# ADJ_REG.net
KiCad netlist of a schematic drawn in Altium Designer
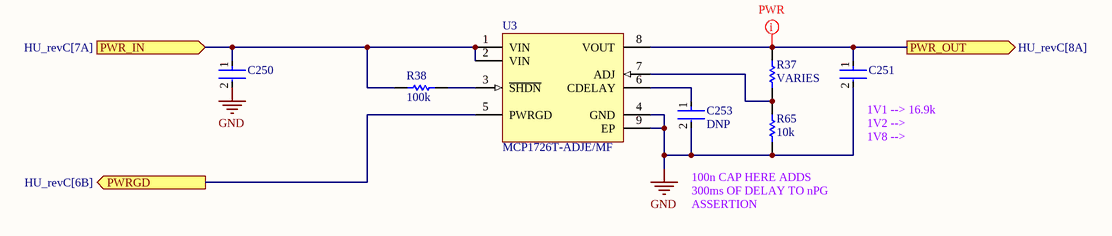
[diagram p0: ADJ_REG.SchDoc]

(export (version "E")
  (design (tool "Eeschema 10.0.6"))
  (components
    (comp (ref "C250")
      (value "C0805C475J4RACAUTO")
      (footprint "FP-C0805C475J4RACAUTO-MFG")
      (description "C0805C475J4RACAUTO Cap Ceramic 4.7uF 16V X7R 5% Pad SMD 0805 125C Automotive T/R")
      (fields (field (name "TOLERANCE") "5%"))
      (libsource (lib "Altium Content Vault") (part "b4654b650e69147ec39a6b967a45e02"))
    )
    (comp (ref "C251")
      (value "GRM21BR61E226ME44L")
      (footprint "FP-GRM21B-0_2-e0_2_0_7-IPC_B")
      (description "Chip Multilayer Ceramic Capacitors for General Purpose, 0805, 22uF, X5R, 15%, 20%, 25V")
      (fields (field (name "TOLERANCE") "20%") (field (name "VOLTAGE") "25V"))
      (libsource (lib "Altium Content Vault") (part "b4654b650e69147ec39a6b967a45e02"))
    )
    (comp (ref "C253")
      (value "DNP")
      (footprint "FP-0402-L_1_0_0_05-W_0_5-IPC_A")
      (description "LARGE PADS, 0402 CAP, CHANGE COMMENT TO MATCH REAL P/N")
      (libsource (lib "Space Concordia") (part "b4654b650e69147ec39a6b967a45e02"))
    )
    (comp (ref "R37")
      (value "VARIES")
      (footprint "R0603B")
      (description "Resistor")
      (libsource (lib "Space Concordia") (part "Resistor"))
    )
    (comp (ref "R38")
      (value "100k")
      (footprint "R0603B")
      (description "Resistor")
      (libsource (lib "Space Concordia") (part "Resistor"))
    )
    (comp (ref "R65")
      (value "10k")
      (footprint "R0603B")
      (description "Resistor")
      (libsource (lib "Space Concordia") (part "Resistor"))
    )
    (comp (ref "U3")
      (value "MCP1726T-ADJE/MF")
      (footprint "DFN-MF8")
      (libsource (lib "Altium Content Vault") (part "PM-LINEREG-MCP1726-IL9A"))
    )
  )
  (nets
    (net (code "1") (name "/PWRGD") (class "Default")
      (node (ref "U3") (pin "5") (pinfunction "PWRGD_5") (pintype "power_in"))
    )
    (net (code "2") (name "/PWR_IN") (class "Default")
      (node (ref "C250") (pin "1") (pinfunction "1_1") (pintype "passive"))
      (node (ref "R38") (pin "1") (pinfunction "1_1") (pintype "passive"))
      (node (ref "U3") (pin "1") (pinfunction "VIN_1") (pintype "power_in"))
      (node (ref "U3") (pin "2") (pinfunction "VIN_2") (pintype "power_in"))
    )
    (net (code "3") (name "/PWR_OUT") (class "Default")
      (node (ref "C251") (pin "1") (pinfunction "1_1") (pintype "passive"))
      (node (ref "R37") (pin "2") (pinfunction "2_2") (pintype "passive"))
      (node (ref "U3") (pin "8") (pinfunction "VOUT_8") (pintype "power_in"))
    )
    (net (code "4") (name "GND") (class "Default")
      (node (ref "C250") (pin "2") (pinfunction "2_2") (pintype "passive"))
      (node (ref "C251") (pin "2") (pinfunction "2_2") (pintype "passive"))
      (node (ref "C253") (pin "2") (pinfunction "2_2") (pintype "passive"))
      (node (ref "R65") (pin "1") (pinfunction "1_1") (pintype "passive"))
      (node (ref "U3") (pin "4") (pinfunction "GND_4") (pintype "power_in"))
      (node (ref "U3") (pin "9") (pinfunction "EP_9") (pintype "power_in"))
    )
    (net (code "5") (name "Net-(U3-ADJ)") (class "Default")
      (node (ref "R37") (pin "1") (pinfunction "1_1") (pintype "passive"))
      (node (ref "R65") (pin "2") (pinfunction "2_2") (pintype "passive"))
      (node (ref "U3") (pin "7") (pinfunction "ADJ_7") (pintype "input"))
    )
    (net (code "6") (name "Net-(U3-CDELAY)") (class "Default")
      (node (ref "C253") (pin "1") (pinfunction "1_1") (pintype "passive"))
      (node (ref "U3") (pin "6") (pinfunction "CDELAY_6") (pintype "passive"))
    )
    (net (code "7") (name "Net-(U3-~{SHDN})") (class "Default")
      (node (ref "R38") (pin "2") (pinfunction "2_2") (pintype "passive"))
      (node (ref "U3") (pin "3") (pinfunction "~{SHDN}_3") (pintype "input"))
    )
  )
)
